# DMMSwitchBoard.net
KiCad netlist of a schematic drawn in Altium Designer
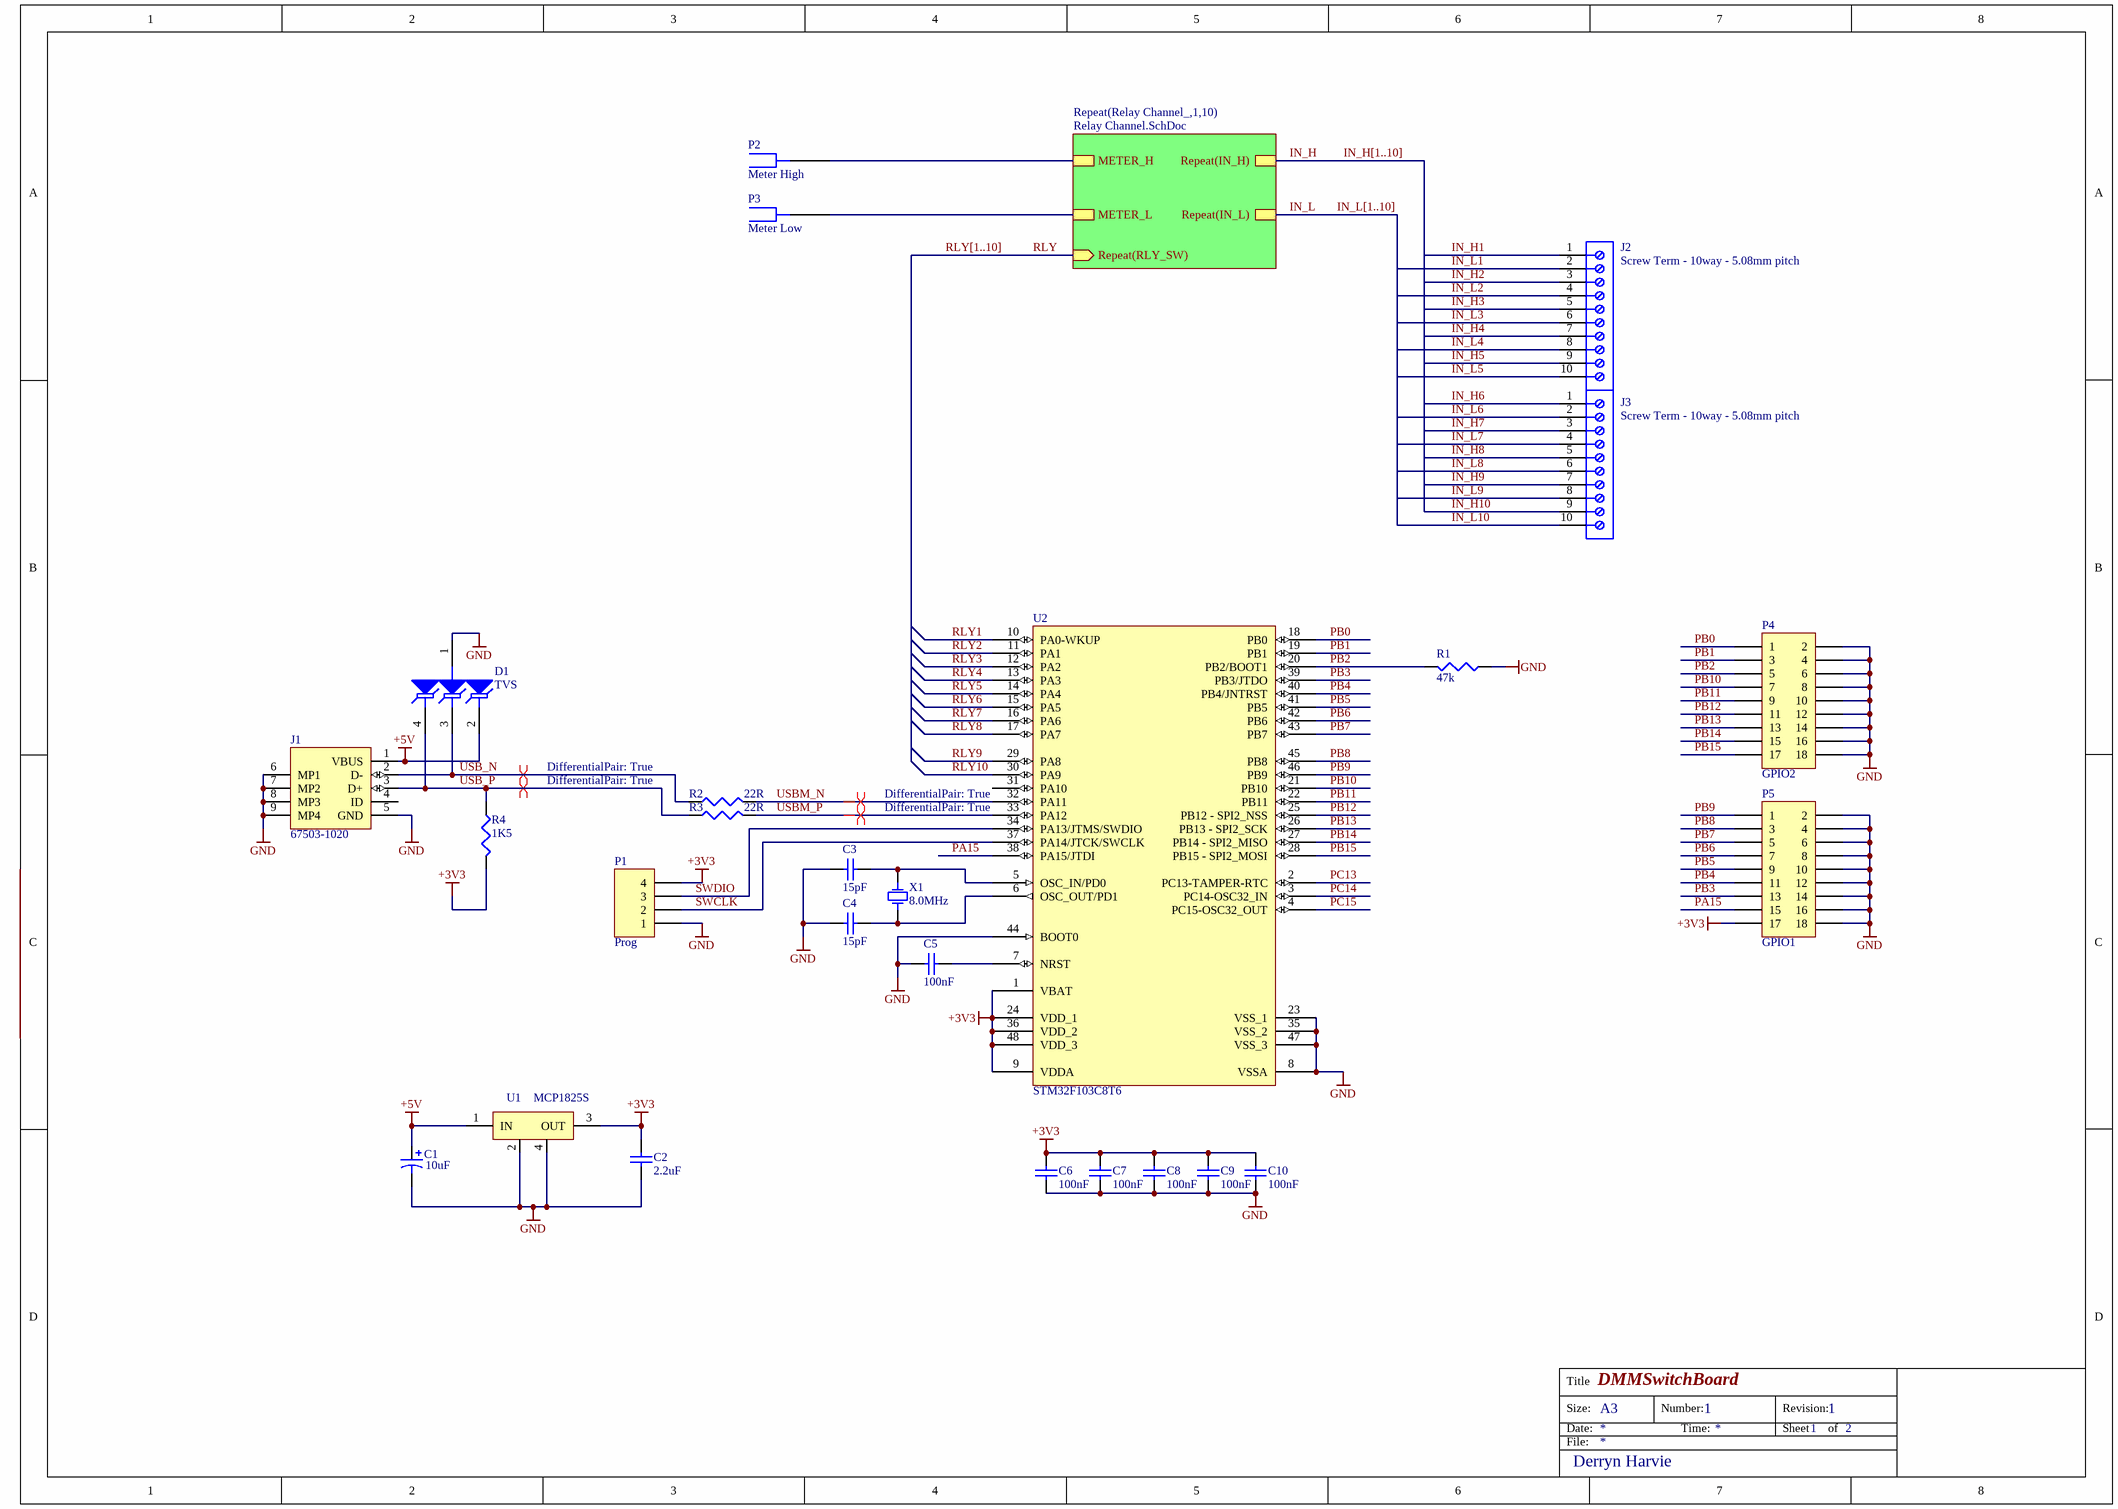
[diagram p0: DMMSwitchBoard.SchDoc]

(export (version "E")
  (design (tool "Eeschema 10.0.6"))
  (components
    (comp (ref "C1")
      (value "10uF")
      (footprint "0805")
      (description "Surface Mount Tantalum Capacitor")
      (fields (field (name "Comment") "Cap Pol2"))
      (libsource (lib "MainLib") (part "Tantalum Capacitor"))
    )
    (comp (ref "C2")
      (value "2.2uF")
      (footprint "0603")
      (description "Ceramic Chip Capacitor - Standard")
      (fields (field (name "Comment") "C0603") (field (name "PUBLISHER") "Altium Limited"))
      (libsource (lib "MainLib") (part "C0603"))
    )
    (comp (ref "C3")
      (value "15pF")
      (footprint "0603")
      (description "Ceramic Chip Capacitor - Standard")
      (fields (field (name "Comment") "C0603") (field (name "PUBLISHER") "Altium Limited"))
      (libsource (lib "MainLib") (part "C0603"))
    )
    (comp (ref "C4")
      (value "15pF")
      (footprint "0603")
      (description "Ceramic Chip Capacitor - Standard")
      (fields (field (name "Comment") "C0603") (field (name "PUBLISHER") "Altium Limited"))
      (libsource (lib "MainLib") (part "C0603"))
    )
    (comp (ref "C5")
      (value "100nF")
      (footprint "0603")
      (description "Ceramic Chip Capacitor - Standard")
      (fields (field (name "Comment") "C0603") (field (name "PUBLISHER") "Altium Limited"))
      (libsource (lib "MainLib") (part "C0603"))
    )
    (comp (ref "C6")
      (value "100nF")
      (footprint "0603")
      (description "Ceramic Chip Capacitor - Standard")
      (fields (field (name "Comment") "C0603") (field (name "PUBLISHER") "Altium Limited"))
      (libsource (lib "MainLib") (part "C0603"))
    )
    (comp (ref "C7")
      (value "100nF")
      (footprint "0603")
      (description "Ceramic Chip Capacitor - Standard")
      (fields (field (name "Comment") "C0603") (field (name "PUBLISHER") "Altium Limited"))
      (libsource (lib "MainLib") (part "C0603"))
    )
    (comp (ref "C8")
      (value "100nF")
      (footprint "0603")
      (description "Ceramic Chip Capacitor - Standard")
      (fields (field (name "Comment") "C0603") (field (name "PUBLISHER") "Altium Limited"))
      (libsource (lib "MainLib") (part "C0603"))
    )
    (comp (ref "C9")
      (value "100nF")
      (footprint "0603")
      (description "Ceramic Chip Capacitor - Standard")
      (fields (field (name "Comment") "C0603") (field (name "PUBLISHER") "Altium Limited"))
      (libsource (lib "MainLib") (part "C0603"))
    )
    (comp (ref "C10")
      (value "100nF")
      (footprint "0603")
      (description "Ceramic Chip Capacitor - Standard")
      (fields (field (name "Comment") "C0603") (field (name "PUBLISHER") "Altium Limited"))
      (libsource (lib "MainLib") (part "C0603"))
    )
    (comp (ref "D1")
      (value "TVS")
      (footprint "SOT143-4")
      (description "TVS Array USB")
      (libsource (lib "MainLib") (part "TVS Array - SP0503BAHTG"))
    )
    (comp (ref "J1")
      (value "67503-1020")
      (footprint "MOLX-67503-1020_V")
      (description "USB, MINI, SMD, RA KME04-USBMU03A01")
      (fields (field (name "MANUFACTURER") "Molex"))
      (libsource (lib "Altium Content Vault") (part "MOLX-67503-1020"))
    )
    (comp (ref "J2")
      (value "Screw Term - 10way - 5.08mm pitch")
      (footprint "ST-30W-5.08P")
      (description "Terminal Block, Pitch 5.08mm, 10 Way")
      (libsource (lib "MainSchLib") (part "Screw Term - 10way - 5.08mm pitch"))
    )
    (comp (ref "J3")
      (value "Screw Term - 10way - 5.08mm pitch")
      (footprint "ST-30W-5.08P")
      (description "Terminal Block, Pitch 5.08mm, 10 Way")
      (libsource (lib "MainSchLib") (part "Screw Term - 10way - 5.08mm pitch"))
    )
    (comp (ref "P1")
      (value "Prog")
      (footprint "HDR1X4")
      (description "Header, 4-Pin")
      (fields (field (name "PUBLISHER") "Altium Limited"))
      (libsource (lib "Miscellaneous Connectors") (part "Header 4"))
    )
    (comp (ref "P2")
      (value "Meter High")
      (footprint "Banana_4mm_RA")
      (description "Banana Jack 4mm Right Angle")
      (libsource (lib "MainLib") (part "Jack - Banana - Right Angle"))
    )
    (comp (ref "P3")
      (value "Meter Low")
      (footprint "Banana_4mm_RA")
      (description "Banana Jack 4mm Right Angle")
      (libsource (lib "MainLib") (part "Jack - Banana - Right Angle"))
    )
    (comp (ref "P4")
      (value "GPIO2")
      (footprint "HDR2X9")
      (description "Header, 9-Pin, Dual row")
      (fields (field (name "PUBLISHER") "Altium Limited"))
      (libsource (lib "Miscellaneous Connectors") (part "Header 9X2"))
    )
    (comp (ref "P5")
      (value "GPIO1")
      (footprint "HDR2X9")
      (description "Header, 9-Pin, Dual row")
      (fields (field (name "PUBLISHER") "Altium Limited"))
      (libsource (lib "Miscellaneous Connectors") (part "Header 9X2"))
    )
    (comp (ref "R1")
      (value "47k")
      (footprint "0603")
      (description "Resistor")
      (libsource (lib "DataRecorderSchLib") (part "Resistor"))
    )
    (comp (ref "R2")
      (value "22R")
      (footprint "0603")
      (description "Resistor")
      (libsource (lib "DataRecorderSchLib") (part "Resistor"))
    )
    (comp (ref "R3")
      (value "22R")
      (footprint "0603")
      (description "Resistor")
      (libsource (lib "DataRecorderSchLib") (part "Resistor"))
    )
    (comp (ref "R4")
      (value "1K5")
      (footprint "0603")
      (description "Resistor")
      (libsource (lib "DataRecorderSchLib") (part "Resistor"))
    )
    (comp (ref "U1")
      (value "MCP1825S")
      (footprint "SOT223")
      (description "IC REG LDO 3.3V 0.5A SOT223-3")
      (fields
        (field (name "MANUFACTURER") "Microchip Technology")
        (field (name "MANUFACTURER PART NUMBER") "MCP1825S-3302E/DB")
      )
      (libsource (lib "DataRecorderSchLib") (part "MCP1825S-3302E/DB"))
    )
    (comp (ref "U2")
      (value "STM32F103C8T6")
      (footprint "LQFP48_L")
      (description "STM32 ARM-based 32-bit MCU with 64 Kbytes Flash, 48-pin LQFP, Industrial Temperature")
      (fields (field (name "MANUFACTURER") "STMicroelectronics"))
      (libsource (lib "DataRecorderSchLib") (part "STM32F103C8T6"))
    )
    (comp (ref "X1")
      (value "8.0MHz")
      (footprint "8MHz Crystal")
      (description "ABRACON - ABL-8.000MHZ-B2. - CRYSTAL, 8MHZ, 18PF, HC-49US")
      (fields
        (field (name "MANUFACTURER") "ABRACON")
        (field (name "MANUFACTURER PART NUMBER") "ABL-8.000MHZ-B2.")
      )
      (libsource (lib "SdLoggerLibs") (part "ABL-8.000MHZ-B2."))
    )
  )
  (nets
    (net (code "1") (name "+3V3") (class "Default")
      (node (ref "C10") (pin "1") (pinfunction "1_1") (pintype "passive"))
      (node (ref "C2") (pin "1") (pinfunction "1_1") (pintype "passive"))
      (node (ref "C6") (pin "1") (pinfunction "1_1") (pintype "passive"))
      (node (ref "C7") (pin "1") (pinfunction "1_1") (pintype "passive"))
      (node (ref "C8") (pin "1") (pinfunction "1_1") (pintype "passive"))
      (node (ref "C9") (pin "1") (pinfunction "1_1") (pintype "passive"))
      (node (ref "P1") (pin "4") (pinfunction "4_4") (pintype "passive"))
      (node (ref "P5") (pin "17") (pinfunction "17_17") (pintype "passive"))
      (node (ref "R4") (pin "2") (pinfunction "2_2") (pintype "passive"))
      (node (ref "U1") (pin "3") (pinfunction "OUT_3") (pintype "power_in"))
      (node (ref "U2") (pin "1") (pinfunction "VBAT_1") (pintype "power_in"))
      (node (ref "U2") (pin "24") (pinfunction "VDD_1_24") (pintype "power_in"))
      (node (ref "U2") (pin "36") (pinfunction "VDD_2_36") (pintype "power_in"))
      (node (ref "U2") (pin "48") (pinfunction "VDD_3_48") (pintype "power_in"))
      (node (ref "U2") (pin "9") (pinfunction "VDDA_9") (pintype "power_in"))
    )
    (net (code "2") (name "+5V") (class "Default")
      (node (ref "C1") (pin "1") (pinfunction "1_1") (pintype "passive"))
      (node (ref "D1") (pin "2") (pinfunction "2_2") (pintype "passive"))
      (node (ref "J1") (pin "1") (pinfunction "VBUS_1") (pintype "power_in"))
      (node (ref "U1") (pin "1") (pinfunction "IN_1") (pintype "power_in"))
    )
    (net (code "4") (name "/IN_H1") (class "Default")
      (node (ref "J2") (pin "1") (pinfunction "1_1") (pintype "passive"))
    )
    (net (code "5") (name "/IN_H2") (class "Default")
      (node (ref "J2") (pin "3") (pinfunction "3_3") (pintype "passive"))
    )
    (net (code "6") (name "/IN_H3") (class "Default")
      (node (ref "J2") (pin "5") (pinfunction "5_5") (pintype "passive"))
    )
    (net (code "7") (name "/IN_H4") (class "Default")
      (node (ref "J2") (pin "7") (pinfunction "7_7") (pintype "passive"))
    )
    (net (code "8") (name "/IN_H5") (class "Default")
      (node (ref "J2") (pin "9") (pinfunction "9_9") (pintype "passive"))
    )
    (net (code "9") (name "/IN_H6") (class "Default")
      (node (ref "J3") (pin "1") (pinfunction "1_1") (pintype "passive"))
    )
    (net (code "10") (name "/IN_H7") (class "Default")
      (node (ref "J3") (pin "3") (pinfunction "3_3") (pintype "passive"))
    )
    (net (code "11") (name "/IN_H8") (class "Default")
      (node (ref "J3") (pin "5") (pinfunction "5_5") (pintype "passive"))
    )
    (net (code "12") (name "/IN_H9") (class "Default")
      (node (ref "J3") (pin "7") (pinfunction "7_7") (pintype "passive"))
    )
    (net (code "13") (name "/IN_H10") (class "Default")
      (node (ref "J3") (pin "9") (pinfunction "9_9") (pintype "passive"))
    )
    (net (code "16") (name "/IN_L1") (class "Default")
      (node (ref "J2") (pin "2") (pinfunction "2_2") (pintype "passive"))
    )
    (net (code "17") (name "/IN_L2") (class "Default")
      (node (ref "J2") (pin "4") (pinfunction "4_4") (pintype "passive"))
    )
    (net (code "18") (name "/IN_L3") (class "Default")
      (node (ref "J2") (pin "6") (pinfunction "6_6") (pintype "passive"))
    )
    (net (code "19") (name "/IN_L4") (class "Default")
      (node (ref "J2") (pin "8") (pinfunction "8_8") (pintype "passive"))
    )
    (net (code "20") (name "/IN_L5") (class "Default")
      (node (ref "J2") (pin "10") (pinfunction "10_10") (pintype "passive"))
    )
    (net (code "21") (name "/IN_L6") (class "Default")
      (node (ref "J3") (pin "2") (pinfunction "2_2") (pintype "passive"))
    )
    (net (code "22") (name "/IN_L7") (class "Default")
      (node (ref "J3") (pin "4") (pinfunction "4_4") (pintype "passive"))
    )
    (net (code "23") (name "/IN_L8") (class "Default")
      (node (ref "J3") (pin "6") (pinfunction "6_6") (pintype "passive"))
    )
    (net (code "24") (name "/IN_L9") (class "Default")
      (node (ref "J3") (pin "8") (pinfunction "8_8") (pintype "passive"))
    )
    (net (code "25") (name "/IN_L10") (class "Default")
      (node (ref "J3") (pin "10") (pinfunction "10_10") (pintype "passive"))
    )
    (net (code "27") (name "/METER_H") (class "Default")
      (node (ref "P2") (pin "1") (pinfunction "1_1") (pintype "passive"))
    )
    (net (code "28") (name "/METER_L") (class "Default")
      (node (ref "P3") (pin "1") (pinfunction "1_1") (pintype "passive"))
    )
    (net (code "29") (name "/PA15") (class "Default")
      (node (ref "P5") (pin "15") (pinfunction "15_15") (pintype "passive"))
      (node (ref "U2") (pin "38") (pinfunction "PA15/JTDI_38") (pintype "bidirectional"))
    )
    (net (code "30") (name "/PB0") (class "Default")
      (node (ref "P4") (pin "1") (pinfunction "1_1") (pintype "passive"))
      (node (ref "U2") (pin "18") (pinfunction "PB0_18") (pintype "bidirectional"))
    )
    (net (code "31") (name "/PB1") (class "Default")
      (node (ref "P4") (pin "3") (pinfunction "3_3") (pintype "passive"))
      (node (ref "U2") (pin "19") (pinfunction "PB1_19") (pintype "bidirectional"))
    )
    (net (code "32") (name "/PB2") (class "Default")
      (node (ref "P4") (pin "5") (pinfunction "5_5") (pintype "passive"))
      (node (ref "R1") (pin "2") (pinfunction "2_2") (pintype "passive"))
      (node (ref "U2") (pin "20") (pinfunction "PB2/BOOT1_20") (pintype "bidirectional"))
    )
    (net (code "33") (name "/PB3") (class "Default")
      (node (ref "P5") (pin "13") (pinfunction "13_13") (pintype "passive"))
      (node (ref "U2") (pin "39") (pinfunction "PB3/JTDO_39") (pintype "bidirectional"))
    )
    (net (code "34") (name "/PB4") (class "Default")
      (node (ref "P5") (pin "11") (pinfunction "11_11") (pintype "passive"))
      (node (ref "U2") (pin "40") (pinfunction "PB4/JNTRST_40") (pintype "bidirectional"))
    )
    (net (code "35") (name "/PB5") (class "Default")
      (node (ref "P5") (pin "9") (pinfunction "9_9") (pintype "passive"))
      (node (ref "U2") (pin "41") (pinfunction "PB5_41") (pintype "bidirectional"))
    )
    (net (code "36") (name "/PB6") (class "Default")
      (node (ref "P5") (pin "7") (pinfunction "7_7") (pintype "passive"))
      (node (ref "U2") (pin "42") (pinfunction "PB6_42") (pintype "bidirectional"))
    )
    (net (code "37") (name "/PB7") (class "Default")
      (node (ref "P5") (pin "5") (pinfunction "5_5") (pintype "passive"))
      (node (ref "U2") (pin "43") (pinfunction "PB7_43") (pintype "bidirectional"))
    )
    (net (code "38") (name "/PB8") (class "Default")
      (node (ref "P5") (pin "3") (pinfunction "3_3") (pintype "passive"))
      (node (ref "U2") (pin "45") (pinfunction "PB8_45") (pintype "bidirectional"))
    )
    (net (code "39") (name "/PB9") (class "Default")
      (node (ref "P5") (pin "1") (pinfunction "1_1") (pintype "passive"))
      (node (ref "U2") (pin "46") (pinfunction "PB9_46") (pintype "bidirectional"))
    )
    (net (code "40") (name "/PB10") (class "Default")
      (node (ref "P4") (pin "7") (pinfunction "7_7") (pintype "passive"))
      (node (ref "U2") (pin "21") (pinfunction "PB10_21") (pintype "bidirectional"))
    )
    (net (code "41") (name "/PB11") (class "Default")
      (node (ref "P4") (pin "9") (pinfunction "9_9") (pintype "passive"))
      (node (ref "U2") (pin "22") (pinfunction "PB11_22") (pintype "bidirectional"))
    )
    (net (code "42") (name "/PB12") (class "Default")
      (node (ref "P4") (pin "11") (pinfunction "11_11") (pintype "passive"))
      (node (ref "U2") (pin "25") (pinfunction "PB12_-_SPI2_NSS_25") (pintype "bidirectional"))
    )
    (net (code "43") (name "/PB13") (class "Default")
      (node (ref "P4") (pin "13") (pinfunction "13_13") (pintype "passive"))
      (node (ref "U2") (pin "26") (pinfunction "PB13_-_SPI2_SCK_26") (pintype "bidirectional"))
    )
    (net (code "44") (name "/PB14") (class "Default")
      (node (ref "P4") (pin "15") (pinfunction "15_15") (pintype "passive"))
      (node (ref "U2") (pin "27") (pinfunction "PB14_-_SPI2_MISO_27") (pintype "bidirectional"))
    )
    (net (code "45") (name "/PB15") (class "Default")
      (node (ref "P4") (pin "17") (pinfunction "17_17") (pintype "passive"))
      (node (ref "U2") (pin "28") (pinfunction "PB15_-_SPI2_MOSI_28") (pintype "bidirectional"))
    )
    (net (code "46") (name "/PC13") (class "Default")
      (node (ref "U2") (pin "2") (pinfunction "PC13-TAMPER-RTC_2") (pintype "bidirectional"))
    )
    (net (code "47") (name "/PC14") (class "Default")
      (node (ref "U2") (pin "3") (pinfunction "PC14-OSC32_IN_3") (pintype "bidirectional"))
    )
    (net (code "48") (name "/PC15") (class "Default")
      (node (ref "U2") (pin "4") (pinfunction "PC15-OSC32_OUT_4") (pintype "bidirectional"))
    )
    (net (code "50") (name "/RLY1") (class "Default")
      (node (ref "U2") (pin "10") (pinfunction "PA0-WKUP_10") (pintype "bidirectional"))
    )
    (net (code "51") (name "/RLY2") (class "Default")
      (node (ref "U2") (pin "11") (pinfunction "PA1_11") (pintype "bidirectional"))
    )
    (net (code "52") (name "/RLY3") (class "Default")
      (node (ref "U2") (pin "12") (pinfunction "PA2_12") (pintype "bidirectional"))
    )
    (net (code "53") (name "/RLY4") (class "Default")
      (node (ref "U2") (pin "13") (pinfunction "PA3_13") (pintype "bidirectional"))
    )
    (net (code "54") (name "/RLY5") (class "Default")
      (node (ref "U2") (pin "14") (pinfunction "PA4_14") (pintype "bidirectional"))
    )
    (net (code "55") (name "/RLY6") (class "Default")
      (node (ref "U2") (pin "15") (pinfunction "PA5_15") (pintype "bidirectional"))
    )
    (net (code "56") (name "/RLY7") (class "Default")
      (node (ref "U2") (pin "16") (pinfunction "PA6_16") (pintype "bidirectional"))
    )
    (net (code "57") (name "/RLY8") (class "Default")
      (node (ref "U2") (pin "17") (pinfunction "PA7_17") (pintype "bidirectional"))
    )
    (net (code "58") (name "/RLY9") (class "Default")
      (node (ref "U2") (pin "29") (pinfunction "PA8_29") (pintype "bidirectional"))
    )
    (net (code "59") (name "/RLY10") (class "Default")
      (node (ref "U2") (pin "30") (pinfunction "PA9_30") (pintype "bidirectional"))
    )
    (net (code "61") (name "/SWCLK") (class "Default")
      (node (ref "P1") (pin "2") (pinfunction "2_2") (pintype "passive"))
      (node (ref "U2") (pin "37") (pinfunction "PA14/JTCK/SWCLK_37") (pintype "bidirectional"))
    )
    (net (code "62") (name "/SWDIO") (class "Default")
      (node (ref "P1") (pin "3") (pinfunction "3_3") (pintype "passive"))
      (node (ref "U2") (pin "34") (pinfunction "PA13/JTMS/SWDIO_34") (pintype "bidirectional"))
    )
    (net (code "63") (name "/USBM_N") (class "Default")
      (node (ref "R2") (pin "2") (pinfunction "2_2") (pintype "passive"))
      (node (ref "U2") (pin "32") (pinfunction "PA11_32") (pintype "bidirectional"))
    )
    (net (code "64") (name "/USBM_P") (class "Default")
      (node (ref "R3") (pin "2") (pinfunction "2_2") (pintype "passive"))
      (node (ref "U2") (pin "33") (pinfunction "PA12_33") (pintype "bidirectional"))
    )
    (net (code "65") (name "/USB_N") (class "Default")
      (node (ref "D1") (pin "3") (pinfunction "3_3") (pintype "passive"))
      (node (ref "J1") (pin "2") (pinfunction "D-_2") (pintype "bidirectional"))
      (node (ref "R2") (pin "1") (pinfunction "1_1") (pintype "passive"))
    )
    (net (code "66") (name "/USB_P") (class "Default")
      (node (ref "D1") (pin "4") (pinfunction "4_4") (pintype "passive"))
      (node (ref "J1") (pin "3") (pinfunction "D+_3") (pintype "bidirectional"))
      (node (ref "R3") (pin "1") (pinfunction "1_1") (pintype "passive"))
      (node (ref "R4") (pin "1") (pinfunction "1_1") (pintype "passive"))
    )
    (net (code "67") (name "GND") (class "Default")
      (node (ref "C1") (pin "2") (pinfunction "2_2") (pintype "passive"))
      (node (ref "C10") (pin "2") (pinfunction "2_2") (pintype "passive"))
      (node (ref "C2") (pin "2") (pinfunction "2_2") (pintype "passive"))
      (node (ref "C3") (pin "1") (pinfunction "1_1") (pintype "passive"))
      (node (ref "C4") (pin "1") (pinfunction "1_1") (pintype "passive"))
      (node (ref "C5") (pin "1") (pinfunction "1_1") (pintype "passive"))
      (node (ref "C6") (pin "2") (pinfunction "2_2") (pintype "passive"))
      (node (ref "C7") (pin "2") (pinfunction "2_2") (pintype "passive"))
      (node (ref "C8") (pin "2") (pinfunction "2_2") (pintype "passive"))
      (node (ref "C9") (pin "2") (pinfunction "2_2") (pintype "passive"))
      (node (ref "D1") (pin "1") (pinfunction "1_1") (pintype "passive"))
      (node (ref "J1") (pin "5") (pinfunction "GND_5") (pintype "power_in"))
      (node (ref "J1") (pin "6") (pinfunction "MP1_6") (pintype "passive"))
      (node (ref "J1") (pin "7") (pinfunction "MP2_7") (pintype "passive"))
      (node (ref "J1") (pin "8") (pinfunction "MP3_8") (pintype "passive"))
      (node (ref "J1") (pin "9") (pinfunction "MP4_9") (pintype "passive"))
      (node (ref "P1") (pin "1") (pinfunction "1_1") (pintype "passive"))
      (node (ref "P4") (pin "10") (pinfunction "10_10") (pintype "passive"))
      (node (ref "P4") (pin "12") (pinfunction "12_12") (pintype "passive"))
      (node (ref "P4") (pin "14") (pinfunction "14_14") (pintype "passive"))
      (node (ref "P4") (pin "16") (pinfunction "16_16") (pintype "passive"))
      (node (ref "P4") (pin "18") (pinfunction "18_18") (pintype "passive"))
      (node (ref "P4") (pin "2") (pinfunction "2_2") (pintype "passive"))
      (node (ref "P4") (pin "4") (pinfunction "4_4") (pintype "passive"))
      (node (ref "P4") (pin "6") (pinfunction "6_6") (pintype "passive"))
      (node (ref "P4") (pin "8") (pinfunction "8_8") (pintype "passive"))
      (node (ref "P5") (pin "10") (pinfunction "10_10") (pintype "passive"))
      (node (ref "P5") (pin "12") (pinfunction "12_12") (pintype "passive"))
      (node (ref "P5") (pin "14") (pinfunction "14_14") (pintype "passive"))
      (node (ref "P5") (pin "16") (pinfunction "16_16") (pintype "passive"))
      (node (ref "P5") (pin "18") (pinfunction "18_18") (pintype "passive"))
      (node (ref "P5") (pin "2") (pinfunction "2_2") (pintype "passive"))
      (node (ref "P5") (pin "4") (pinfunction "4_4") (pintype "passive"))
      (node (ref "P5") (pin "6") (pinfunction "6_6") (pintype "passive"))
      (node (ref "P5") (pin "8") (pinfunction "8_8") (pintype "passive"))
      (node (ref "R1") (pin "1") (pinfunction "1_1") (pintype "passive"))
      (node (ref "U1") (pin "2") (pinfunction "GND@1_2") (pintype "power_in"))
      (node (ref "U1") (pin "4") (pinfunction "GND@2_4") (pintype "power_in"))
      (node (ref "U2") (pin "23") (pinfunction "VSS_1_23") (pintype "power_in"))
      (node (ref "U2") (pin "35") (pinfunction "VSS_2_35") (pintype "power_in"))
      (node (ref "U2") (pin "44") (pinfunction "BOOT0_44") (pintype "input"))
      (node (ref "U2") (pin "47") (pinfunction "VSS_3_47") (pintype "power_in"))
      (node (ref "U2") (pin "8") (pinfunction "VSSA_8") (pintype "power_in"))
    )
    (net (code "68") (name "Net-(U2-NRST)") (class "Default")
      (node (ref "C5") (pin "2") (pinfunction "2_2") (pintype "passive"))
      (node (ref "U2") (pin "7") (pinfunction "NRST_7") (pintype "bidirectional"))
    )
    (net (code "69") (name "Net-(U2-OSC_IN{slash}PD0)") (class "Default")
      (node (ref "C3") (pin "2") (pinfunction "2_2") (pintype "passive"))
      (node (ref "U2") (pin "5") (pinfunction "OSC_IN/PD0_5") (pintype "input"))
      (node (ref "X1") (pin "2") (pinfunction "2_2") (pintype "passive"))
    )
    (net (code "70") (name "Net-(U2-OSC_OUT{slash}PD1)") (class "Default")
      (node (ref "C4") (pin "2") (pinfunction "2_2") (pintype "passive"))
      (node (ref "U2") (pin "6") (pinfunction "OSC_OUT/PD1_6") (pintype "output"))
      (node (ref "X1") (pin "1") (pinfunction "1_1") (pintype "passive"))
    )
    (net (code "71") (name "unconnected-(J1-ID-Pad4)") (class "Default")
      (node (ref "J1") (pin "4") (pinfunction "ID_4") (pintype "passive"))
    )
    (net (code "72") (name "unconnected-(U2-PA10-Pad31)") (class "Default")
      (node (ref "U2") (pin "31") (pinfunction "PA10_31") (pintype "bidirectional"))
    )
  )
)
